# Sheet_Power.net
KiCad netlist of a schematic drawn in Altium Designer
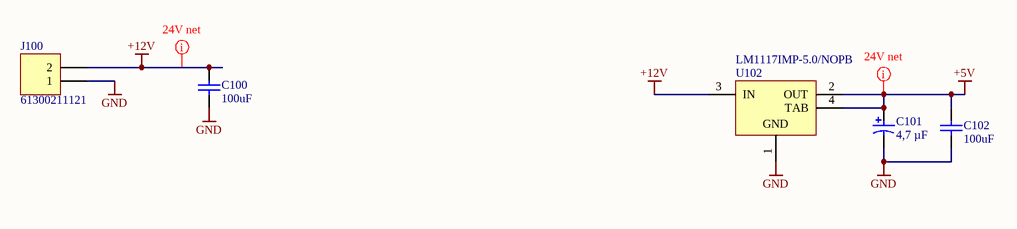
[diagram p0: Sheet_Power.SchDoc]

(export (version "E")
  (design (tool "Eeschema 10.0.6"))
  (components
    (comp (ref "C100")
      (value "100uF")
      (footprint "CAPC1206(3216)190_L")
      (description "CAP 100uF 6.3V ±20% 1206 (3216 Metric) Thickness 1.9mm SMD")
      (fields (field (name "TOLERANCE") "Â±20%") (field (name "PARTNUMBER") "885012108005"))
      (libsource (lib "Altium Vault EMBL 3") (part "CMP-00469-2"))
    )
    (comp (ref "C101")
      (value "4,7 µF")
      (footprint "A Package")
      (description "4,7 µF; 6V; Gr. A; T491A475K006AT")
      (fields (field (name "MANUFACTURER") "KEMET") (field (name "TOLERANCE") "±10%"))
      (libsource (lib "Altium Vault EMBL") (part "CMP-001-0039-3"))
    )
    (comp (ref "C102")
      (value "100uF")
      (footprint "CAPC1206(3216)190_L")
      (description "CAP 100uF 6.3V ±20% 1206 (3216 Metric) Thickness 1.9mm SMD")
      (fields (field (name "TOLERANCE") "Â±20%") (field (name "PARTNUMBER") "885012108005"))
      (libsource (lib "Altium Vault EMBL 3") (part "CMP-00469-2"))
    )
    (comp (ref "J100")
      (value "61300211121")
      (footprint "61300211121")
      (description "2Pol; gerade; WR-PHD 2.54 mm THT Pin Header")
      (fields (field (name "MANUFACTURER") "Wurth Electronics"))
      (libsource (lib "Altium Vault EMBL") (part "CMP-001-0071-1"))
    )
    (comp (ref "U102")
      (value "LM1117IMP-5.0/NOPB")
      (footprint "DCY0004A_M")
      (description "800mA Low-Dropout Linear Regulator, 4-pin SOT-223, Pb-Free")
      (fields (field (name "MANUFACTURER") "Texas Instruments"))
      (libsource (lib "Altium Vault EMBL") (part "CMP-00485-1"))
    )
  )
  (nets
    (net (code "1") (name "+5V") (class "Default")
      (node (ref "C101") (pin "1") (pinfunction "1_1") (pintype "passive"))
      (node (ref "C102") (pin "2") (pinfunction "2_2") (pintype "passive"))
      (node (ref "U102") (pin "2") (pinfunction "OUT_2") (pintype "power_in"))
      (node (ref "U102") (pin "4") (pinfunction "TAB_4") (pintype "power_in"))
    )
    (net (code "2") (name "+12V") (class "Default")
      (node (ref "C100") (pin "2") (pinfunction "2_2") (pintype "passive"))
      (node (ref "J100") (pin "2") (pinfunction "2_2") (pintype "passive"))
      (node (ref "U102") (pin "3") (pinfunction "IN_3") (pintype "power_in"))
    )
    (net (code "3") (name "GND") (class "Default")
      (node (ref "C100") (pin "1") (pinfunction "1_1") (pintype "passive"))
      (node (ref "C101") (pin "2") (pinfunction "2_2") (pintype "passive"))
      (node (ref "C102") (pin "1") (pinfunction "1_1") (pintype "passive"))
      (node (ref "J100") (pin "1") (pinfunction "1_1") (pintype "passive"))
      (node (ref "U102") (pin "1") (pinfunction "GND_1") (pintype "power_in"))
    )
  )
)
